# bt.net
KiCad netlist of a schematic drawn in Altium Designer
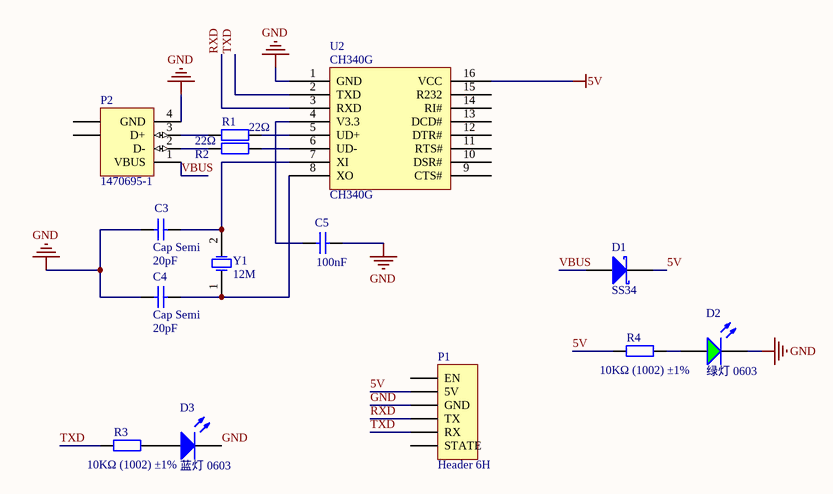
[diagram p0: bt.SchDoc]

(export (version "E")
  (design (tool "Eeschema 10.0.6"))
  (components
    (comp (ref "C3")
      (value "Cap Semi")
      (footprint "C1206")
      (description "Capacitor (Semiconductor SIM Model)")
      (fields (field (name "ALTIUM_VALUE") "20pF") (field (name "PUBLISHER") "Altium Limited"))
      (libsource (lib "Miscellaneous Devices") (part "Cap Semi"))
    )
    (comp (ref "C4")
      (value "Cap Semi")
      (footprint "C1206")
      (description "Capacitor (Semiconductor SIM Model)")
      (fields (field (name "ALTIUM_VALUE") "20pF") (field (name "PUBLISHER") "Altium Limited"))
      (libsource (lib "Miscellaneous Devices") (part "Cap Semi"))
    )
    (comp (ref "C5")
      (value "100nF")
      (footprint "C1206")
      (description "Capacitor (Semiconductor SIM Model)")
      (fields (field (name "Comment") "Cap Semi") (field (name "PUBLISHER") "Altium Limited"))
      (libsource (lib "Miscellaneous Devices") (part "Cap Semi"))
    )
    (comp (ref "D1")
      (value "SS34")
      (footprint "SMB")
      (description "Schottky Diode")
      (fields (field (name "PUBLISHER") "Altium Limited"))
      (libsource (lib "Miscellaneous Devices") (part "D Schottky"))
    )
    (comp (ref "D2")
      (value "绿灯 0603")
      (footprint "0603_LED_S1")
      (description "发光二极管")
      (libsource (lib "Miscellaneous Devices LC") (part "0603 绿灯"))
    )
    (comp (ref "D3")
      (value "蓝灯 0603")
      (footprint "0603_LED_S1")
      (description "发光二极管")
      (libsource (lib "Miscellaneous Devices LC") (part "0603 蓝灯"))
    )
    (comp (ref "P1")
      (value "Header 6H")
      (footprint "HDR1X6H")
      (description "Header, 6-Pin, Right Angle")
      (fields (field (name "PUBLISHER") "Altium Limited"))
      (libsource (lib "Miscellaneous Connectors") (part "Header 6H"))
    )
    (comp (ref "P2")
      (value "1470695-1")
      (footprint "1470695")
      (description "USB 1.1, Right Angle, SMT, A Type, Plug, 4 Position, Natural")
      (fields (field (name "PUBLISHER") "Altium Limited"))
      (libsource (lib "USB") (part "1470695-1"))
    )
    (comp (ref "R1")
      (value "22Ω")
      (footprint "0402_R")
      (description "贴片电阻")
      (libsource (lib "Miscellaneous Devices LC") (part "0402 22Ω (22R0) 1%"))
    )
    (comp (ref "R2")
      (value "22Ω")
      (footprint "0402_R")
      (description "贴片电阻")
      (libsource (lib "Miscellaneous Devices LC") (part "0402 22Ω (22R0) 1%"))
    )
    (comp (ref "R3")
      (value "10KΩ (1002) ±1%")
      (footprint "0402_R")
      (description "贴片电阻")
      (libsource (lib "Miscellaneous Devices LC") (part "0402 10KΩ (1002) 1%"))
    )
    (comp (ref "R4")
      (value "10KΩ (1002) ±1%")
      (footprint "0402_R")
      (description "贴片电阻")
      (libsource (lib "Miscellaneous Devices LC") (part "0402 10KΩ (1002) 1%"))
    )
    (comp (ref "U2")
      (value "CH340G")
      (footprint "SOIC-16_150mil")
      (description "USB")
      (libsource (lib "Miscellaneous Devices LC") (part "CH340G_[C14267]"))
    )
    (comp (ref "Y1")
      (value "12M")
      (footprint "XTAL5")
      (description "Crystal Oscillator")
      (fields (field (name "PUBLISHER") "Altium Limited"))
      (libsource (lib "晶振封装1") (part "XTAL"))
    )
  )
  (nets
    (net (code "1") (name "/RXD") (class "Default")
      (node (ref "P1") (pin "4") (pinfunction "TX_4") (pintype "passive"))
      (node (ref "U2") (pin "3") (pinfunction "RXD_3") (pintype "passive"))
    )
    (net (code "2") (name "/TXD") (class "Default")
      (node (ref "P1") (pin "5") (pinfunction "RX_5") (pintype "passive"))
      (node (ref "R3") (pin "1") (pinfunction "1_1") (pintype "passive"))
      (node (ref "U2") (pin "2") (pinfunction "TXD_2") (pintype "passive"))
    )
    (net (code "3") (name "/VBUS") (class "Default")
      (node (ref "D1") (pin "1") (pinfunction "A_1") (pintype "passive"))
      (node (ref "P2") (pin "1") (pinfunction "VBUS_1") (pintype "power_in"))
    )
    (net (code "4") (name "5V") (class "Default")
      (node (ref "D1") (pin "2") (pinfunction "K_2") (pintype "passive"))
      (node (ref "P1") (pin "2") (pinfunction "5V_2") (pintype "passive"))
      (node (ref "R4") (pin "1") (pinfunction "1_1") (pintype "passive"))
      (node (ref "U2") (pin "16") (pinfunction "VCC_16") (pintype "passive"))
    )
    (net (code "5") (name "GND") (class "Default")
      (node (ref "C3") (pin "2") (pinfunction "2_2") (pintype "passive"))
      (node (ref "C4") (pin "2") (pinfunction "2_2") (pintype "passive"))
      (node (ref "C5") (pin "2") (pinfunction "2_2") (pintype "passive"))
      (node (ref "D2") (pin "K") (pinfunction "K_K") (pintype "passive"))
      (node (ref "D3") (pin "K") (pinfunction "K_K") (pintype "passive"))
      (node (ref "P1") (pin "3") (pinfunction "GND_3") (pintype "passive"))
      (node (ref "P2") (pin "4") (pinfunction "GND_4") (pintype "power_in"))
      (node (ref "U2") (pin "1") (pinfunction "GND_1") (pintype "passive"))
    )
    (net (code "6") (name "Net-(D2-PadA)") (class "Default")
      (node (ref "D2") (pin "A") (pinfunction "A_A") (pintype "passive"))
      (node (ref "R4") (pin "2") (pinfunction "2_2") (pintype "passive"))
    )
    (net (code "7") (name "Net-(D3-PadA)") (class "Default")
      (node (ref "D3") (pin "A") (pinfunction "A_A") (pintype "passive"))
      (node (ref "R3") (pin "2") (pinfunction "2_2") (pintype "passive"))
    )
    (net (code "8") (name "Net-(P2-D+)") (class "Default")
      (node (ref "P2") (pin "3") (pinfunction "D+_3") (pintype "bidirectional"))
      (node (ref "R1") (pin "1") (pinfunction "1_1") (pintype "passive"))
    )
    (net (code "9") (name "Net-(P2-D-)") (class "Default")
      (node (ref "P2") (pin "2") (pinfunction "D-_2") (pintype "bidirectional"))
      (node (ref "R2") (pin "1") (pinfunction "1_1") (pintype "passive"))
    )
    (net (code "10") (name "Net-(U2-UD+)") (class "Default")
      (node (ref "R1") (pin "2") (pinfunction "2_2") (pintype "passive"))
      (node (ref "U2") (pin "5") (pinfunction "UD+_5") (pintype "passive"))
    )
    (net (code "11") (name "Net-(U2-UD-)") (class "Default")
      (node (ref "R2") (pin "2") (pinfunction "2_2") (pintype "passive"))
      (node (ref "U2") (pin "6") (pinfunction "UD-_6") (pintype "passive"))
    )
    (net (code "12") (name "Net-(U2-V3.3)") (class "Default")
      (node (ref "C5") (pin "1") (pinfunction "1_1") (pintype "passive"))
      (node (ref "U2") (pin "4") (pinfunction "V3.3_4") (pintype "passive"))
    )
    (net (code "13") (name "Net-(U2-XI)") (class "Default")
      (node (ref "C3") (pin "1") (pinfunction "1_1") (pintype "passive"))
      (node (ref "U2") (pin "7") (pinfunction "XI_7") (pintype "passive"))
      (node (ref "Y1") (pin "2") (pinfunction "OSC2_2") (pintype "passive"))
    )
    (net (code "14") (name "Net-(U2-XO)") (class "Default")
      (node (ref "C4") (pin "1") (pinfunction "1_1") (pintype "passive"))
      (node (ref "U2") (pin "8") (pinfunction "XO_8") (pintype "passive"))
      (node (ref "Y1") (pin "1") (pinfunction "OSC1_1") (pintype "passive"))
    )
    (net (code "15") (name "unconnected-(P1-EN-Pad1)") (class "Default")
      (node (ref "P1") (pin "1") (pinfunction "EN_1") (pintype "passive"))
    )
    (net (code "16") (name "unconnected-(P1-STATE-Pad6)") (class "Default")
      (node (ref "P1") (pin "6") (pinfunction "STATE_6") (pintype "passive"))
    )
    (net (code "17") (name "unconnected-(P2-SHLD-Pad5)") (class "Default")
      (node (ref "P2") (pin "5") (pinfunction "SHLD_5") (pintype "passive"))
    )
    (net (code "18") (name "unconnected-(P2-SHLD-Pad6)") (class "Default")
      (node (ref "P2") (pin "6") (pinfunction "SHLD_6") (pintype "passive"))
    )
    (net (code "19") (name "unconnected-(U2-CTS#-Pad9)") (class "Default")
      (node (ref "U2") (pin "9") (pinfunction "CTS#_9") (pintype "passive"))
    )
    (net (code "20") (name "unconnected-(U2-DCD#-Pad13)") (class "Default")
      (node (ref "U2") (pin "13") (pinfunction "DCD#_13") (pintype "passive"))
    )
    (net (code "21") (name "unconnected-(U2-DSR#-Pad10)") (class "Default")
      (node (ref "U2") (pin "10") (pinfunction "DSR#_10") (pintype "passive"))
    )
    (net (code "22") (name "unconnected-(U2-DTR#-Pad12)") (class "Default")
      (node (ref "U2") (pin "12") (pinfunction "DTR#_12") (pintype "passive"))
    )
    (net (code "23") (name "unconnected-(U2-R232-Pad15)") (class "Default")
      (node (ref "U2") (pin "15") (pinfunction "R232_15") (pintype "passive"))
    )
    (net (code "24") (name "unconnected-(U2-RI#-Pad14)") (class "Default")
      (node (ref "U2") (pin "14") (pinfunction "RI#_14") (pintype "passive"))
    )
    (net (code "25") (name "unconnected-(U2-RTS#-Pad11)") (class "Default")
      (node (ref "U2") (pin "11") (pinfunction "RTS#_11") (pintype "passive"))
    )
  )
)
